# 23XXAdapter_v1_1.net
KiCad netlist of a schematic drawn in EAGLE
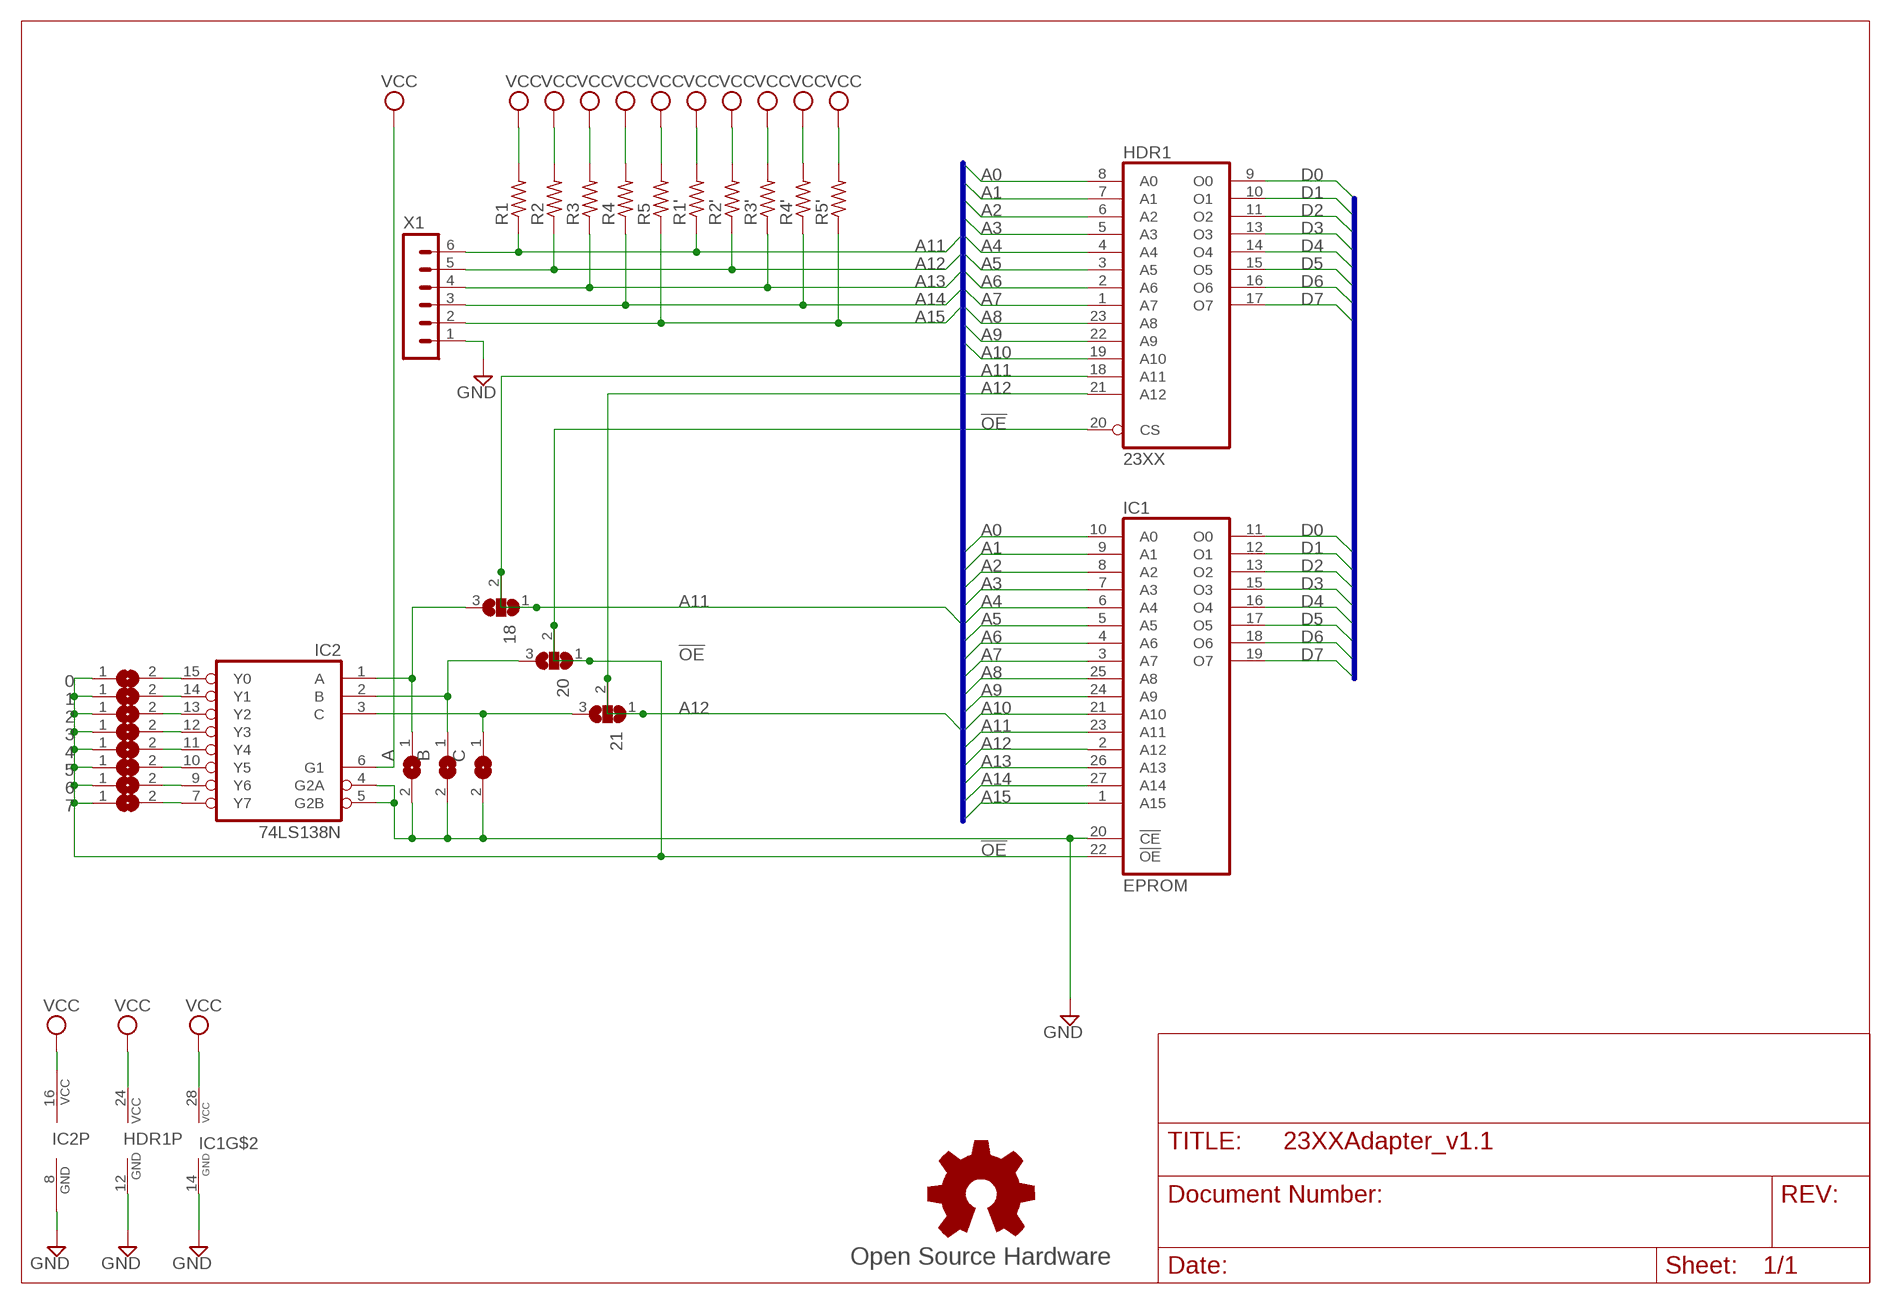
[diagram p0: schematic, sheet 1]

(export (version "E")
  (design (tool "Eeschema 10.0.6"))
  (components
    (comp (ref "0") (value "SJ") (footprint "eagle-import:SJ") (libsource (lib "eagle-import") (part "SJ")))
    (comp (ref "1") (value "SJ") (footprint "eagle-import:SJ") (libsource (lib "eagle-import") (part "SJ")))
    (comp (ref "2") (value "SJ") (footprint "eagle-import:SJ") (libsource (lib "eagle-import") (part "SJ")))
    (comp (ref "3") (value "SJ") (footprint "eagle-import:SJ") (libsource (lib "eagle-import") (part "SJ")))
    (comp (ref "4") (value "SJ") (footprint "eagle-import:SJ") (libsource (lib "eagle-import") (part "SJ")))
    (comp (ref "5") (value "SJ") (footprint "eagle-import:SJ") (libsource (lib "eagle-import") (part "SJ")))
    (comp (ref "6") (value "SJ") (footprint "eagle-import:SJ") (libsource (lib "eagle-import") (part "SJ")))
    (comp (ref "7") (value "SJ") (footprint "eagle-import:SJ") (libsource (lib "eagle-import") (part "SJ")))
    (comp (ref "18")
      (value "SJ2W")
      (footprint "eagle-import:SJ_2")
      (libsource (lib "eagle-import") (part "SJ2W"))
    )
    (comp (ref "20")
      (value "SJ2W")
      (footprint "eagle-import:SJ_2")
      (libsource (lib "eagle-import") (part "SJ2W"))
    )
    (comp (ref "21")
      (value "SJ2W")
      (footprint "eagle-import:SJ_2")
      (libsource (lib "eagle-import") (part "SJ2W"))
    )
    (comp (ref "A") (value "SJ") (footprint "eagle-import:SJ") (libsource (lib "eagle-import") (part "SJ")))
    (comp (ref "B") (value "SJ") (footprint "eagle-import:SJ") (libsource (lib "eagle-import") (part "SJ")))
    (comp (ref "C") (value "SJ") (footprint "eagle-import:SJ") (libsource (lib "eagle-import") (part "SJ")))
    (comp (ref "GOLD_ORB_SM1")
      (value "Open Source Hardware")
      (footprint "eagle-import:OSHW_5MM")
      (libsource (lib "eagle-import") (part "OSHWLOGOLOGO5MM"))
    )
    (comp (ref "HDR1")
      (value "23XX")
      (footprint "eagle-import:DIL24-ROUNDPAD")
      (libsource (lib "eagle-import") (part "2364'RD'"))
    )
    (comp (ref "IC1")
      (value "EPROM")
      (footprint "eagle-import:DIL28-ROUNDPAD")
      (libsource (lib "eagle-import") (part "27512'RD'"))
    )
    (comp (ref "IC2")
      (value "74LS138N")
      (footprint "eagle-import:DIL16-RP")
      (libsource (lib "eagle-import") (part "74138NLS"))
    )
    (comp (ref "R1")
      (value "R-US_0204/5")
      (footprint "eagle-import:0204_5")
      (libsource (lib "eagle-import") (part "R-US_0204/5"))
    )
    (comp (ref "R1'")
      (value "R-US_R0805")
      (footprint "eagle-import:R0805")
      (libsource (lib "eagle-import") (part "R-US_R0805"))
    )
    (comp (ref "R2")
      (value "R-US_0204/5")
      (footprint "eagle-import:0204_5")
      (libsource (lib "eagle-import") (part "R-US_0204/5"))
    )
    (comp (ref "R2'")
      (value "R-US_R0805")
      (footprint "eagle-import:R0805")
      (libsource (lib "eagle-import") (part "R-US_R0805"))
    )
    (comp (ref "R3")
      (value "R-US_0204/5")
      (footprint "eagle-import:0204_5")
      (libsource (lib "eagle-import") (part "R-US_0204/5"))
    )
    (comp (ref "R3'")
      (value "R-US_R0805")
      (footprint "eagle-import:R0805")
      (libsource (lib "eagle-import") (part "R-US_R0805"))
    )
    (comp (ref "R4")
      (value "R-US_0204/5")
      (footprint "eagle-import:0204_5")
      (libsource (lib "eagle-import") (part "R-US_0204/5"))
    )
    (comp (ref "R4'")
      (value "R-US_R0805")
      (footprint "eagle-import:R0805")
      (libsource (lib "eagle-import") (part "R-US_R0805"))
    )
    (comp (ref "R5")
      (value "R-US_0204/5")
      (footprint "eagle-import:0204_5")
      (libsource (lib "eagle-import") (part "R-US_0204/5"))
    )
    (comp (ref "R5'")
      (value "R-US_R0805")
      (footprint "eagle-import:R0805")
      (libsource (lib "eagle-import") (part "R-US_R0805"))
    )
    (comp (ref "X1")
      (value "MA06-1")
      (footprint "eagle-import:MA06-1")
      (libsource (lib "eagle-import") (part "MA06-1"))
    )
  )
  (nets
    (net (code "1") (name "/A0") (class "Default")
      (node (ref "HDR1") (pin "8") (pinfunction "A0_8") (pintype "input"))
      (node (ref "IC1") (pin "10") (pinfunction "A0_10") (pintype "input"))
    )
    (net (code "2") (name "/A1") (class "Default")
      (node (ref "HDR1") (pin "7") (pinfunction "A1_7") (pintype "input"))
      (node (ref "IC1") (pin "9") (pinfunction "A1_9") (pintype "input"))
    )
    (net (code "3") (name "/A2") (class "Default")
      (node (ref "HDR1") (pin "6") (pinfunction "A2_6") (pintype "input"))
      (node (ref "IC1") (pin "8") (pinfunction "A2_8") (pintype "input"))
    )
    (net (code "4") (name "/A3") (class "Default")
      (node (ref "HDR1") (pin "5") (pinfunction "A3_5") (pintype "input"))
      (node (ref "IC1") (pin "7") (pinfunction "A3_7") (pintype "input"))
    )
    (net (code "5") (name "/A4") (class "Default")
      (node (ref "HDR1") (pin "4") (pinfunction "A4_4") (pintype "input"))
      (node (ref "IC1") (pin "6") (pinfunction "A4_6") (pintype "input"))
    )
    (net (code "6") (name "/A5") (class "Default")
      (node (ref "HDR1") (pin "3") (pinfunction "A5_3") (pintype "input"))
      (node (ref "IC1") (pin "5") (pinfunction "A5_5") (pintype "input"))
    )
    (net (code "7") (name "/A6") (class "Default")
      (node (ref "HDR1") (pin "2") (pinfunction "A6_2") (pintype "input"))
      (node (ref "IC1") (pin "4") (pinfunction "A6_4") (pintype "input"))
    )
    (net (code "8") (name "/A7") (class "Default")
      (node (ref "HDR1") (pin "1") (pinfunction "A7_1") (pintype "input"))
      (node (ref "IC1") (pin "3") (pinfunction "A7_3") (pintype "input"))
    )
    (net (code "9") (name "/A8") (class "Default")
      (node (ref "HDR1") (pin "23") (pinfunction "A8_23") (pintype "input"))
      (node (ref "IC1") (pin "25") (pinfunction "A8_25") (pintype "input"))
    )
    (net (code "10") (name "/A9") (class "Default")
      (node (ref "HDR1") (pin "22") (pinfunction "A9_22") (pintype "input"))
      (node (ref "IC1") (pin "24") (pinfunction "A9_24") (pintype "input"))
    )
    (net (code "11") (name "/A10") (class "Default")
      (node (ref "HDR1") (pin "19") (pinfunction "A10_19") (pintype "input"))
      (node (ref "IC1") (pin "21") (pinfunction "A10_21") (pintype "input"))
    )
    (net (code "12") (name "/A11") (class "Default")
      (node (ref "18") (pin "1") (pinfunction "1_1") (pintype "passive"))
      (node (ref "18") (pin "2") (pinfunction "2_2") (pintype "passive"))
      (node (ref "HDR1") (pin "18") (pinfunction "A11_18") (pintype "input"))
      (node (ref "IC1") (pin "23") (pinfunction "A11_23") (pintype "input"))
      (node (ref "R1") (pin "1") (pinfunction "1_1") (pintype "passive"))
      (node (ref "R1'") (pin "1") (pinfunction "1_1") (pintype "passive"))
      (node (ref "X1") (pin "6") (pinfunction "6_6") (pintype "passive"))
    )
    (net (code "13") (name "/A12") (class "Default")
      (node (ref "21") (pin "1") (pinfunction "1_1") (pintype "passive"))
      (node (ref "21") (pin "2") (pinfunction "2_2") (pintype "passive"))
      (node (ref "HDR1") (pin "21") (pinfunction "A12_21") (pintype "input"))
      (node (ref "IC1") (pin "2") (pinfunction "A12_2") (pintype "input"))
      (node (ref "R2") (pin "1") (pinfunction "1_1") (pintype "passive"))
      (node (ref "R2'") (pin "1") (pinfunction "1_1") (pintype "passive"))
      (node (ref "X1") (pin "5") (pinfunction "5_5") (pintype "passive"))
    )
    (net (code "14") (name "/A13") (class "Default")
      (node (ref "IC1") (pin "26") (pinfunction "A13_26") (pintype "input"))
      (node (ref "R3") (pin "1") (pinfunction "1_1") (pintype "passive"))
      (node (ref "R3'") (pin "1") (pinfunction "1_1") (pintype "passive"))
      (node (ref "X1") (pin "4") (pinfunction "4_4") (pintype "passive"))
    )
    (net (code "15") (name "/A14") (class "Default")
      (node (ref "IC1") (pin "27") (pinfunction "A14_27") (pintype "input"))
      (node (ref "R4") (pin "1") (pinfunction "1_1") (pintype "passive"))
      (node (ref "R4'") (pin "1") (pinfunction "1_1") (pintype "passive"))
      (node (ref "X1") (pin "3") (pinfunction "3_3") (pintype "passive"))
    )
    (net (code "16") (name "/A15") (class "Default")
      (node (ref "IC1") (pin "1") (pinfunction "A15_1") (pintype "input"))
      (node (ref "R5") (pin "1") (pinfunction "1_1") (pintype "passive"))
      (node (ref "R5'") (pin "1") (pinfunction "1_1") (pintype "passive"))
      (node (ref "X1") (pin "2") (pinfunction "2_2") (pintype "passive"))
    )
    (net (code "17") (name "/D0") (class "Default")
      (node (ref "HDR1") (pin "9") (pinfunction "O0_9") (pintype "tri_state"))
      (node (ref "IC1") (pin "11") (pinfunction "O0_11") (pintype "tri_state"))
    )
    (net (code "18") (name "/D1") (class "Default")
      (node (ref "HDR1") (pin "10") (pinfunction "O1_10") (pintype "tri_state"))
      (node (ref "IC1") (pin "12") (pinfunction "O1_12") (pintype "tri_state"))
    )
    (net (code "19") (name "/D2") (class "Default")
      (node (ref "HDR1") (pin "11") (pinfunction "O2_11") (pintype "tri_state"))
      (node (ref "IC1") (pin "13") (pinfunction "O2_13") (pintype "tri_state"))
    )
    (net (code "20") (name "/D3") (class "Default")
      (node (ref "HDR1") (pin "13") (pinfunction "O3_13") (pintype "tri_state"))
      (node (ref "IC1") (pin "15") (pinfunction "O3_15") (pintype "tri_state"))
    )
    (net (code "21") (name "/D4") (class "Default")
      (node (ref "HDR1") (pin "14") (pinfunction "O4_14") (pintype "tri_state"))
      (node (ref "IC1") (pin "16") (pinfunction "O4_16") (pintype "tri_state"))
    )
    (net (code "22") (name "/D5") (class "Default")
      (node (ref "HDR1") (pin "15") (pinfunction "O5_15") (pintype "tri_state"))
      (node (ref "IC1") (pin "17") (pinfunction "O5_17") (pintype "tri_state"))
    )
    (net (code "23") (name "/D6") (class "Default")
      (node (ref "HDR1") (pin "16") (pinfunction "O6_16") (pintype "tri_state"))
      (node (ref "IC1") (pin "18") (pinfunction "O6_18") (pintype "tri_state"))
    )
    (net (code "24") (name "/D7") (class "Default")
      (node (ref "HDR1") (pin "17") (pinfunction "O7_17") (pintype "tri_state"))
      (node (ref "IC1") (pin "19") (pinfunction "O7_19") (pintype "tri_state"))
    )
    (net (code "25") (name "/~{OE}") (class "Default")
      (node (ref "0") (pin "1") (pinfunction "1_1") (pintype "passive"))
      (node (ref "1") (pin "1") (pinfunction "1_1") (pintype "passive"))
      (node (ref "2") (pin "1") (pinfunction "1_1") (pintype "passive"))
      (node (ref "20") (pin "1") (pinfunction "1_1") (pintype "passive"))
      (node (ref "20") (pin "2") (pinfunction "2_2") (pintype "passive"))
      (node (ref "3") (pin "1") (pinfunction "1_1") (pintype "passive"))
      (node (ref "4") (pin "1") (pinfunction "1_1") (pintype "passive"))
      (node (ref "5") (pin "1") (pinfunction "1_1") (pintype "passive"))
      (node (ref "6") (pin "1") (pinfunction "1_1") (pintype "passive"))
      (node (ref "7") (pin "1") (pinfunction "1_1") (pintype "passive"))
      (node (ref "HDR1") (pin "20") (pinfunction "CS_20") (pintype "input"))
      (node (ref "IC1") (pin "22") (pinfunction "~{OE}_22") (pintype "input"))
    )
    (net (code "26") (name "GND") (class "Default")
      (node (ref "A") (pin "2") (pinfunction "2_2") (pintype "passive"))
      (node (ref "B") (pin "2") (pinfunction "2_2") (pintype "passive"))
      (node (ref "C") (pin "2") (pinfunction "2_2") (pintype "passive"))
      (node (ref "HDR1") (pin "12") (pinfunction "GND_12") (pintype "power_in"))
      (node (ref "IC1") (pin "14") (pinfunction "GND_14") (pintype "power_in"))
      (node (ref "IC1") (pin "20") (pinfunction "~{CE}_20") (pintype "input"))
      (node (ref "IC2") (pin "4") (pinfunction "G2A_4") (pintype "input"))
      (node (ref "IC2") (pin "5") (pinfunction "G2B_5") (pintype "input"))
      (node (ref "IC2") (pin "8") (pinfunction "GND_8") (pintype "power_in"))
      (node (ref "X1") (pin "1") (pinfunction "1_1") (pintype "passive"))
    )
    (net (code "27") (name "Net-(IC2A-A)") (class "Default")
      (node (ref "18") (pin "3") (pinfunction "3_3") (pintype "passive"))
      (node (ref "A") (pin "1") (pinfunction "1_1") (pintype "passive"))
      (node (ref "IC2") (pin "1") (pinfunction "A_1") (pintype "input"))
    )
    (net (code "28") (name "Net-(IC2A-B)") (class "Default")
      (node (ref "20") (pin "3") (pinfunction "3_3") (pintype "passive"))
      (node (ref "B") (pin "1") (pinfunction "1_1") (pintype "passive"))
      (node (ref "IC2") (pin "2") (pinfunction "B_2") (pintype "input"))
    )
    (net (code "29") (name "Net-(IC2A-C)") (class "Default")
      (node (ref "21") (pin "3") (pinfunction "3_3") (pintype "passive"))
      (node (ref "C") (pin "1") (pinfunction "1_1") (pintype "passive"))
      (node (ref "IC2") (pin "3") (pinfunction "C_3") (pintype "input"))
    )
    (net (code "30") (name "Net-(IC2A-Y0)") (class "Default")
      (node (ref "0") (pin "2") (pinfunction "2_2") (pintype "passive"))
      (node (ref "IC2") (pin "15") (pinfunction "Y0_15") (pintype "output"))
    )
    (net (code "31") (name "Net-(IC2A-Y1)") (class "Default")
      (node (ref "1") (pin "2") (pinfunction "2_2") (pintype "passive"))
      (node (ref "IC2") (pin "14") (pinfunction "Y1_14") (pintype "output"))
    )
    (net (code "32") (name "Net-(IC2A-Y2)") (class "Default")
      (node (ref "2") (pin "2") (pinfunction "2_2") (pintype "passive"))
      (node (ref "IC2") (pin "13") (pinfunction "Y2_13") (pintype "output"))
    )
    (net (code "33") (name "Net-(IC2A-Y3)") (class "Default")
      (node (ref "3") (pin "2") (pinfunction "2_2") (pintype "passive"))
      (node (ref "IC2") (pin "12") (pinfunction "Y3_12") (pintype "output"))
    )
    (net (code "34") (name "Net-(IC2A-Y4)") (class "Default")
      (node (ref "4") (pin "2") (pinfunction "2_2") (pintype "passive"))
      (node (ref "IC2") (pin "11") (pinfunction "Y4_11") (pintype "output"))
    )
    (net (code "35") (name "Net-(IC2A-Y5)") (class "Default")
      (node (ref "5") (pin "2") (pinfunction "2_2") (pintype "passive"))
      (node (ref "IC2") (pin "10") (pinfunction "Y5_10") (pintype "output"))
    )
    (net (code "36") (name "Net-(IC2A-Y6)") (class "Default")
      (node (ref "6") (pin "2") (pinfunction "2_2") (pintype "passive"))
      (node (ref "IC2") (pin "9") (pinfunction "Y6_9") (pintype "output"))
    )
    (net (code "37") (name "Net-(IC2A-Y7)") (class "Default")
      (node (ref "7") (pin "2") (pinfunction "2_2") (pintype "passive"))
      (node (ref "IC2") (pin "7") (pinfunction "Y7_7") (pintype "output"))
    )
    (net (code "38") (name "VCC") (class "Default")
      (node (ref "HDR1") (pin "24") (pinfunction "VCC_24") (pintype "power_in"))
      (node (ref "IC1") (pin "28") (pinfunction "VCC_28") (pintype "power_in"))
      (node (ref "IC2") (pin "16") (pinfunction "VCC_16") (pintype "power_in"))
      (node (ref "IC2") (pin "6") (pinfunction "G1_6") (pintype "input"))
      (node (ref "R1") (pin "2") (pinfunction "2_2") (pintype "passive"))
      (node (ref "R1'") (pin "2") (pinfunction "2_2") (pintype "passive"))
      (node (ref "R2") (pin "2") (pinfunction "2_2") (pintype "passive"))
      (node (ref "R2'") (pin "2") (pinfunction "2_2") (pintype "passive"))
      (node (ref "R3") (pin "2") (pinfunction "2_2") (pintype "passive"))
      (node (ref "R3'") (pin "2") (pinfunction "2_2") (pintype "passive"))
      (node (ref "R4") (pin "2") (pinfunction "2_2") (pintype "passive"))
      (node (ref "R4'") (pin "2") (pinfunction "2_2") (pintype "passive"))
      (node (ref "R5") (pin "2") (pinfunction "2_2") (pintype "passive"))
      (node (ref "R5'") (pin "2") (pinfunction "2_2") (pintype "passive"))
    )
  )
)
